# DE-120418.net
KiCad netlist of a schematic drawn in Altium Designer
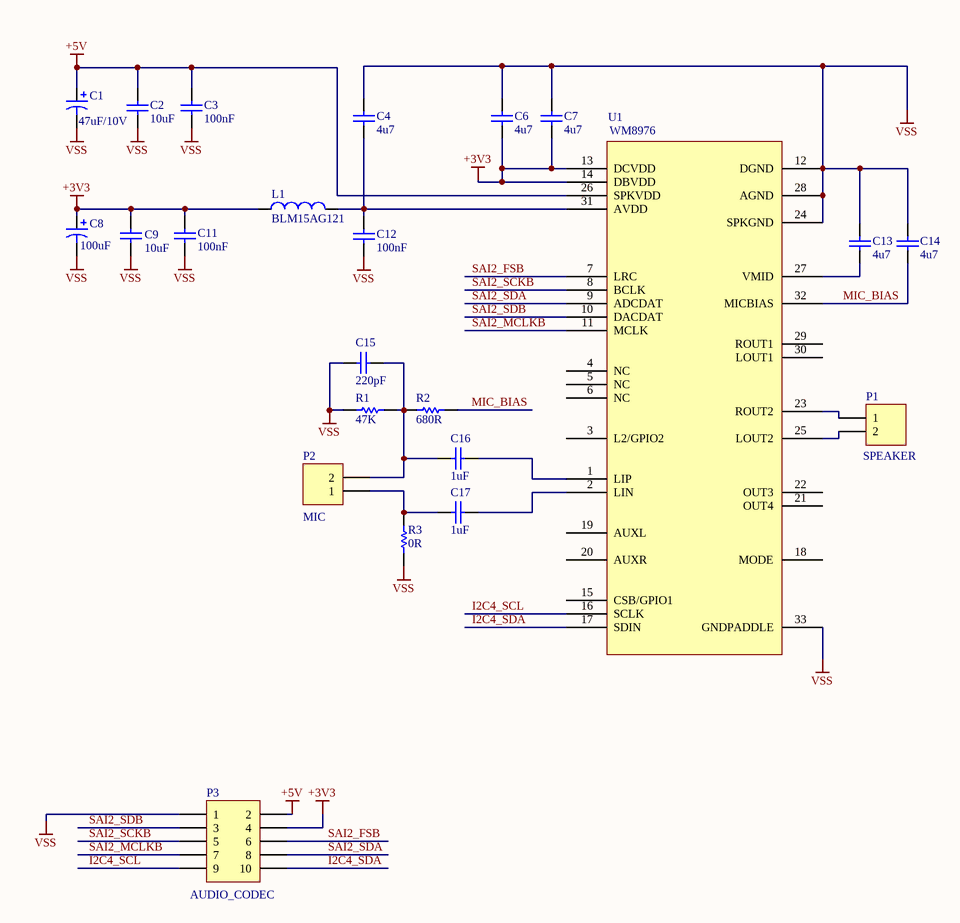
[diagram p0: DE-120418.SchDoc]

(export (version "E")
  (design (tool "Eeschema 10.0.6"))
  (components
    (comp (ref "C1")
      (value "47uF/10V")
      (footprint "3528")
      (fields (field (name "PUBLISHER") "Altium Limited"))
      (libsource (lib "Vishay Sprague Tantalum Chip Capacitor") (part "293D156X0004B2"))
    )
    (comp (ref "C2")
      (value "10uF")
      (footprint "0805")
      (description "Ceramic Chip Capacitor - Standard")
      (fields (field (name "PUBLISHER") "Altium Limited"))
      (libsource (lib "DE-251215") (part "C0805"))
    )
    (comp (ref "C3")
      (value "100nF")
      (footprint "0603")
      (description "Ceramic Chip Capacitor - Standard")
      (fields (field (name "PUBLISHER") "Altium Limited"))
      (libsource (lib "DE-120418") (part "C0603"))
    )
    (comp (ref "C4")
      (value "4u7")
      (footprint "0805")
      (description "Ceramic Chip Capacitor - Standard")
      (fields (field (name "PUBLISHER") "Altium Limited"))
      (libsource (lib "DE-020717") (part "C0805"))
    )
    (comp (ref "C6")
      (value "4u7")
      (footprint "0805")
      (description "Ceramic Chip Capacitor - Standard")
      (fields (field (name "PUBLISHER") "Altium Limited"))
      (libsource (lib "DE-020717") (part "C0805"))
    )
    (comp (ref "C7")
      (value "4u7")
      (footprint "0805")
      (description "Ceramic Chip Capacitor - Standard")
      (fields (field (name "PUBLISHER") "Altium Limited"))
      (libsource (lib "DE-020717") (part "C0805"))
    )
    (comp (ref "C8")
      (value "100uF")
      (footprint "3528")
      (fields (field (name "PUBLISHER") "Altium Limited"))
      (libsource (lib "Vishay Sprague Tantalum Chip Capacitor") (part "293D156X0004B2"))
    )
    (comp (ref "C9")
      (value "10uF")
      (footprint "0805")
      (description "Ceramic Chip Capacitor - Standard")
      (fields (field (name "PUBLISHER") "Altium Limited"))
      (libsource (lib "DE-251215") (part "C0805"))
    )
    (comp (ref "C11")
      (value "100nF")
      (footprint "0603")
      (description "Ceramic Chip Capacitor - Standard")
      (fields (field (name "PUBLISHER") "Altium Limited"))
      (libsource (lib "DE-120418") (part "C0603"))
    )
    (comp (ref "C12")
      (value "100nF")
      (footprint "0603")
      (description "Ceramic Chip Capacitor - Standard")
      (fields (field (name "PUBLISHER") "Altium Limited"))
      (libsource (lib "DE-120418") (part "C0603"))
    )
    (comp (ref "C13")
      (value "4u7")
      (footprint "0805")
      (description "Ceramic Chip Capacitor - Standard")
      (fields (field (name "PUBLISHER") "Altium Limited"))
      (libsource (lib "DE-020717") (part "C0805"))
    )
    (comp (ref "C14")
      (value "4u7")
      (footprint "0805")
      (description "Ceramic Chip Capacitor - Standard")
      (fields (field (name "PUBLISHER") "Altium Limited"))
      (libsource (lib "DE-020717") (part "C0805"))
    )
    (comp (ref "C15")
      (value "220pF")
      (footprint "0603")
      (description "Ceramic Chip Capacitor - Standard")
      (fields (field (name "PUBLISHER") "Altium Limited"))
      (libsource (lib "DE-020717") (part "C0603"))
    )
    (comp (ref "C16")
      (value "1uF")
      (footprint "0603")
      (description "Ceramic Chip Capacitor - Standard")
      (fields (field (name "PUBLISHER") "Altium Limited"))
      (libsource (lib "DE-120418") (part "C0603"))
    )
    (comp (ref "C17")
      (value "1uF")
      (footprint "0603")
      (description "Ceramic Chip Capacitor - Standard")
      (fields (field (name "PUBLISHER") "Altium Limited"))
      (libsource (lib "DE-120418") (part "C0603"))
    )
    (comp (ref "L1")
      (value "BLM15AG121")
      (footprint "INDC1608L")
      (description "Inductor")
      (fields (field (name "PUBLISHER") "Altium Limited"))
      (libsource (lib "DE-020717") (part "Inductor_SMD"))
    )
    (comp (ref "P1")
      (value "SPEAKER")
      (footprint "HDR1X2")
      (description "Header, 2-Pin")
      (fields (field (name "PUBLISHER") "Altium Limited"))
      (libsource (lib "") (part "Header 2_1"))
    )
    (comp (ref "P2")
      (value "MIC")
      (footprint "HDR1X2")
      (description "Header, 2-Pin")
      (fields (field (name "PUBLISHER") "Altium Limited"))
      (libsource (lib "Miscellaneous Connectors") (part "Header 2"))
    )
    (comp (ref "P3")
      (value "AUDIO_CODEC")
      (footprint "HDR2X5")
      (description "Header, 5-Pin, Dual row")
      (fields (field (name "PUBLISHER") "Altium Limited"))
      (libsource (lib "Miscellaneous Connectors") (part "Header 5X2"))
    )
    (comp (ref "R1")
      (value "47K")
      (footprint "ERA-0603")
      (fields (field (name "PUBLISHER") "Altium Limited"))
      (libsource (lib "DE-200216_03") (part "ERAV"))
    )
    (comp (ref "R2")
      (value "680R")
      (footprint "ERA-0603")
      (fields (field (name "PUBLISHER") "Altium Limited"))
      (libsource (lib "DE-200216_03") (part "ERAV"))
    )
    (comp (ref "R3")
      (value "0R")
      (footprint "ERA-0603")
      (fields (field (name "PUBLISHER") "Altium Limited"))
      (libsource (lib "DE-200216_03") (part "ERAV"))
    )
    (comp (ref "U1")
      (value "WM8976")
      (footprint "QFN32_N")
      (description "Stereo CODEC with speaker driver")
      (libsource (lib "DE-020717") (part "WM8976"))
    )
  )
  (nets
    (net (code "1") (name "+3V3") (class "Default")
      (node (ref "C11") (pin "2") (pinfunction "2_2") (pintype "passive"))
      (node (ref "C6") (pin "2") (pinfunction "2_2") (pintype "passive"))
      (node (ref "C7") (pin "2") (pinfunction "2_2") (pintype "passive"))
      (node (ref "C8") (pin "1") (pinfunction "1_1") (pintype "passive"))
      (node (ref "C9") (pin "2") (pinfunction "2_2") (pintype "passive"))
      (node (ref "L1") (pin "1") (pinfunction "1_1") (pintype "passive"))
      (node (ref "P3") (pin "4") (pinfunction "4_4") (pintype "passive"))
      (node (ref "U1") (pin "13") (pinfunction "DCVDD_13") (pintype "power_in"))
      (node (ref "U1") (pin "14") (pinfunction "DBVDD_14") (pintype "power_in"))
    )
    (net (code "2") (name "+5V") (class "Default")
      (node (ref "C1") (pin "1") (pinfunction "1_1") (pintype "passive"))
      (node (ref "C2") (pin "2") (pinfunction "2_2") (pintype "passive"))
      (node (ref "C3") (pin "2") (pinfunction "2_2") (pintype "passive"))
      (node (ref "P3") (pin "2") (pinfunction "2_2") (pintype "passive"))
      (node (ref "U1") (pin "26") (pinfunction "SPKVDD_26") (pintype "power_in"))
    )
    (net (code "3") (name "/I2C4_SCL") (class "Default")
      (node (ref "P3") (pin "9") (pinfunction "9_9") (pintype "passive"))
      (node (ref "U1") (pin "16") (pinfunction "SCLK_16") (pintype "passive"))
    )
    (net (code "4") (name "/I2C4_SDA") (class "Default")
      (node (ref "P3") (pin "10") (pinfunction "10_10") (pintype "passive"))
      (node (ref "U1") (pin "17") (pinfunction "SDIN_17") (pintype "passive"))
    )
    (net (code "5") (name "/MIC_BIAS") (class "Default")
      (node (ref "C14") (pin "2") (pinfunction "2_2") (pintype "passive"))
      (node (ref "R2") (pin "1") (pinfunction "1_1") (pintype "passive"))
      (node (ref "U1") (pin "32") (pinfunction "MICBIAS_32") (pintype "power_in"))
    )
    (net (code "6") (name "/SAI2_FSB") (class "Default")
      (node (ref "P3") (pin "6") (pinfunction "6_6") (pintype "passive"))
      (node (ref "U1") (pin "7") (pinfunction "LRC_7") (pintype "passive"))
    )
    (net (code "7") (name "/SAI2_MCLKB") (class "Default")
      (node (ref "P3") (pin "7") (pinfunction "7_7") (pintype "passive"))
      (node (ref "U1") (pin "11") (pinfunction "MCLK_11") (pintype "passive"))
    )
    (net (code "8") (name "/SAI2_SCKB") (class "Default")
      (node (ref "P3") (pin "5") (pinfunction "5_5") (pintype "passive"))
      (node (ref "U1") (pin "8") (pinfunction "BCLK_8") (pintype "passive"))
    )
    (net (code "9") (name "/SAI2_SDA") (class "Default")
      (node (ref "P3") (pin "8") (pinfunction "8_8") (pintype "passive"))
      (node (ref "U1") (pin "9") (pinfunction "ADCDAT_9") (pintype "passive"))
    )
    (net (code "10") (name "/SAI2_SDB") (class "Default")
      (node (ref "P3") (pin "3") (pinfunction "3_3") (pintype "passive"))
      (node (ref "U1") (pin "10") (pinfunction "DACDAT_10") (pintype "passive"))
    )
    (net (code "11") (name "Net-(C15-Pad2)") (class "Default")
      (node (ref "C15") (pin "2") (pinfunction "2_2") (pintype "passive"))
      (node (ref "C16") (pin "1") (pinfunction "1_1") (pintype "passive"))
      (node (ref "P2") (pin "2") (pinfunction "2_2") (pintype "passive"))
      (node (ref "R1") (pin "1") (pinfunction "1_1") (pintype "passive"))
      (node (ref "R2") (pin "2") (pinfunction "2_2") (pintype "passive"))
    )
    (net (code "12") (name "Net-(C17-Pad1)") (class "Default")
      (node (ref "C17") (pin "1") (pinfunction "1_1") (pintype "passive"))
      (node (ref "P2") (pin "1") (pinfunction "1_1") (pintype "passive"))
      (node (ref "R3") (pin "2") (pinfunction "2_2") (pintype "passive"))
    )
    (net (code "13") (name "Net-(U1-AVDD)") (class "Default")
      (node (ref "C12") (pin "2") (pinfunction "2_2") (pintype "passive"))
      (node (ref "C4") (pin "2") (pinfunction "2_2") (pintype "passive"))
      (node (ref "L1") (pin "2") (pinfunction "2_2") (pintype "passive"))
      (node (ref "U1") (pin "31") (pinfunction "AVDD_31") (pintype "power_in"))
    )
    (net (code "14") (name "Net-(U1-LIN)") (class "Default")
      (node (ref "C17") (pin "2") (pinfunction "2_2") (pintype "passive"))
      (node (ref "U1") (pin "2") (pinfunction "LIN_2") (pintype "passive"))
    )
    (net (code "15") (name "Net-(U1-LIP)") (class "Default")
      (node (ref "C16") (pin "2") (pinfunction "2_2") (pintype "passive"))
      (node (ref "U1") (pin "1") (pinfunction "LIP_1") (pintype "passive"))
    )
    (net (code "16") (name "Net-(U1-LOUT2)") (class "Default")
      (node (ref "P1") (pin "2") (pinfunction "2_2") (pintype "passive"))
      (node (ref "U1") (pin "25") (pinfunction "LOUT2_25") (pintype "passive"))
    )
    (net (code "17") (name "Net-(U1-ROUT2)") (class "Default")
      (node (ref "P1") (pin "1") (pinfunction "1_1") (pintype "passive"))
      (node (ref "U1") (pin "23") (pinfunction "ROUT2_23") (pintype "passive"))
    )
    (net (code "18") (name "Net-(U1-VMID)") (class "Default")
      (node (ref "C13") (pin "2") (pinfunction "2_2") (pintype "passive"))
      (node (ref "U1") (pin "27") (pinfunction "VMID_27") (pintype "power_in"))
    )
    (net (code "19") (name "VSS") (class "Default")
      (node (ref "C1") (pin "2") (pinfunction "2_2") (pintype "passive"))
      (node (ref "C11") (pin "1") (pinfunction "1_1") (pintype "passive"))
      (node (ref "C12") (pin "1") (pinfunction "1_1") (pintype "passive"))
      (node (ref "C13") (pin "1") (pinfunction "1_1") (pintype "passive"))
      (node (ref "C14") (pin "1") (pinfunction "1_1") (pintype "passive"))
      (node (ref "C15") (pin "1") (pinfunction "1_1") (pintype "passive"))
      (node (ref "C2") (pin "1") (pinfunction "1_1") (pintype "passive"))
      (node (ref "C3") (pin "1") (pinfunction "1_1") (pintype "passive"))
      (node (ref "C4") (pin "1") (pinfunction "1_1") (pintype "passive"))
      (node (ref "C6") (pin "1") (pinfunction "1_1") (pintype "passive"))
      (node (ref "C7") (pin "1") (pinfunction "1_1") (pintype "passive"))
      (node (ref "C8") (pin "2") (pinfunction "2_2") (pintype "passive"))
      (node (ref "C9") (pin "1") (pinfunction "1_1") (pintype "passive"))
      (node (ref "P3") (pin "1") (pinfunction "1_1") (pintype "passive"))
      (node (ref "R1") (pin "2") (pinfunction "2_2") (pintype "passive"))
      (node (ref "R3") (pin "1") (pinfunction "1_1") (pintype "passive"))
      (node (ref "U1") (pin "12") (pinfunction "DGND_12") (pintype "power_in"))
      (node (ref "U1") (pin "24") (pinfunction "SPKGND_24") (pintype "power_in"))
      (node (ref "U1") (pin "28") (pinfunction "AGND_28") (pintype "power_in"))
      (node (ref "U1") (pin "33") (pinfunction "GNDPADDLE_33") (pintype "passive"))
    )
    (net (code "20") (name "unconnected-(U1-AUXL-Pad19)") (class "Default")
      (node (ref "U1") (pin "19") (pinfunction "AUXL_19") (pintype "passive"))
    )
    (net (code "21") (name "unconnected-(U1-AUXR-Pad20)") (class "Default")
      (node (ref "U1") (pin "20") (pinfunction "AUXR_20") (pintype "passive"))
    )
    (net (code "22") (name "unconnected-(U1-CSB{slash}GPIO1-Pad15)") (class "Default")
      (node (ref "U1") (pin "15") (pinfunction "CSB/GPIO1_15") (pintype "passive"))
    )
    (net (code "23") (name "unconnected-(U1-L2{slash}GPIO2-Pad3)") (class "Default")
      (node (ref "U1") (pin "3") (pinfunction "L2/GPIO2_3") (pintype "passive"))
    )
    (net (code "24") (name "unconnected-(U1-LOUT1-Pad30)") (class "Default")
      (node (ref "U1") (pin "30") (pinfunction "LOUT1_30") (pintype "passive"))
    )
    (net (code "25") (name "unconnected-(U1-MODE-Pad18)") (class "Default")
      (node (ref "U1") (pin "18") (pinfunction "MODE_18") (pintype "passive"))
    )
    (net (code "26") (name "unconnected-(U1-NC-Pad4)") (class "Default")
      (node (ref "U1") (pin "4") (pinfunction "NC_4") (pintype "passive"))
    )
    (net (code "27") (name "unconnected-(U1-NC-Pad5)") (class "Default")
      (node (ref "U1") (pin "5") (pinfunction "NC_5") (pintype "passive"))
    )
    (net (code "28") (name "unconnected-(U1-NC-Pad6)") (class "Default")
      (node (ref "U1") (pin "6") (pinfunction "NC_6") (pintype "passive"))
    )
    (net (code "29") (name "unconnected-(U1-OUT3-Pad22)") (class "Default")
      (node (ref "U1") (pin "22") (pinfunction "OUT3_22") (pintype "passive"))
    )
    (net (code "30") (name "unconnected-(U1-OUT4-Pad21)") (class "Default")
      (node (ref "U1") (pin "21") (pinfunction "OUT4_21") (pintype "passive"))
    )
    (net (code "31") (name "unconnected-(U1-ROUT1-Pad29)") (class "Default")
      (node (ref "U1") (pin "29") (pinfunction "ROUT1_29") (pintype "passive"))
    )
  )
)
